# 10A_Current_Sensor_v1_0.net
KiCad netlist of a schematic drawn in EAGLE
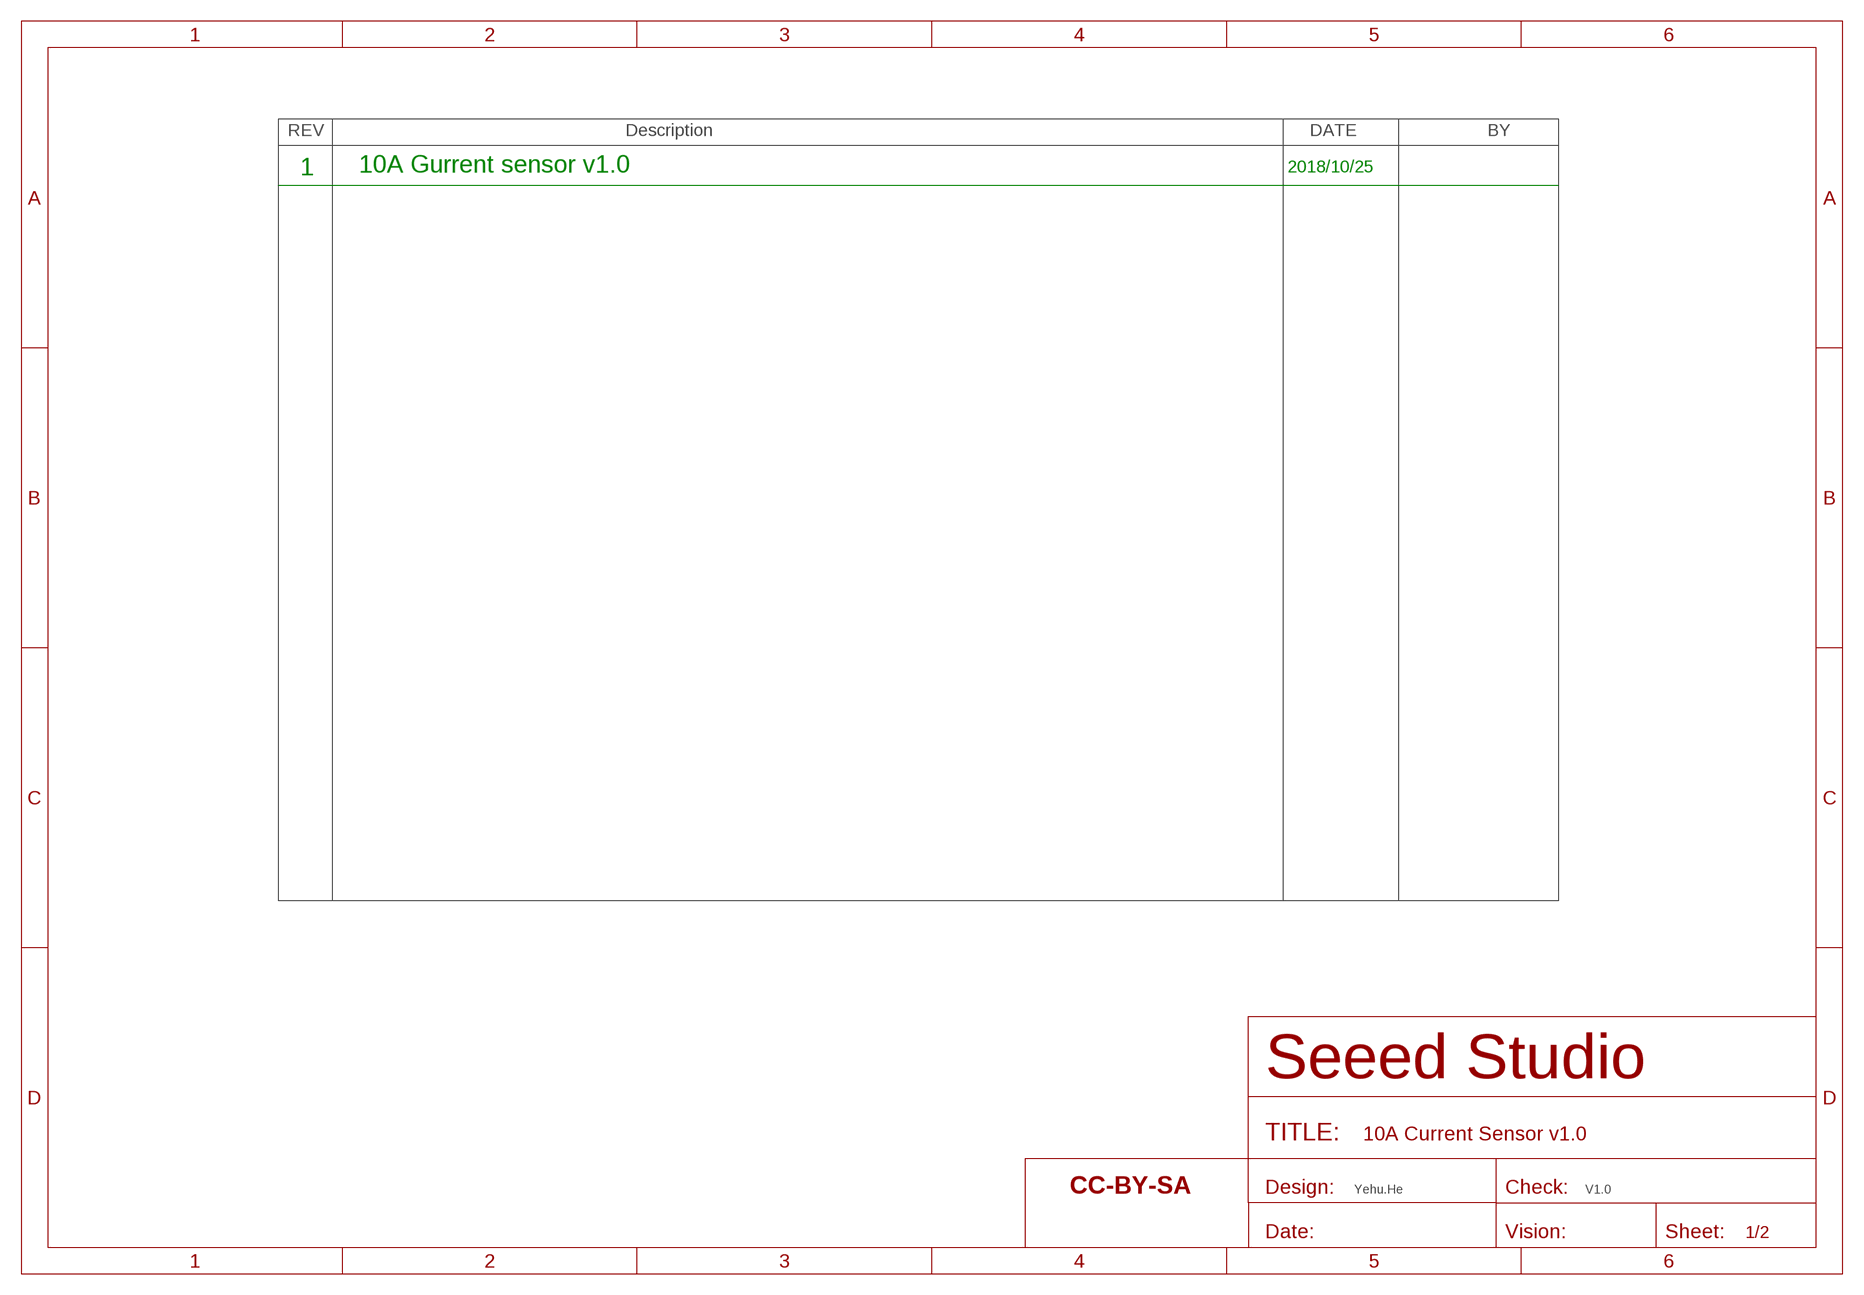
[diagram p0: schematic, sheet 1]
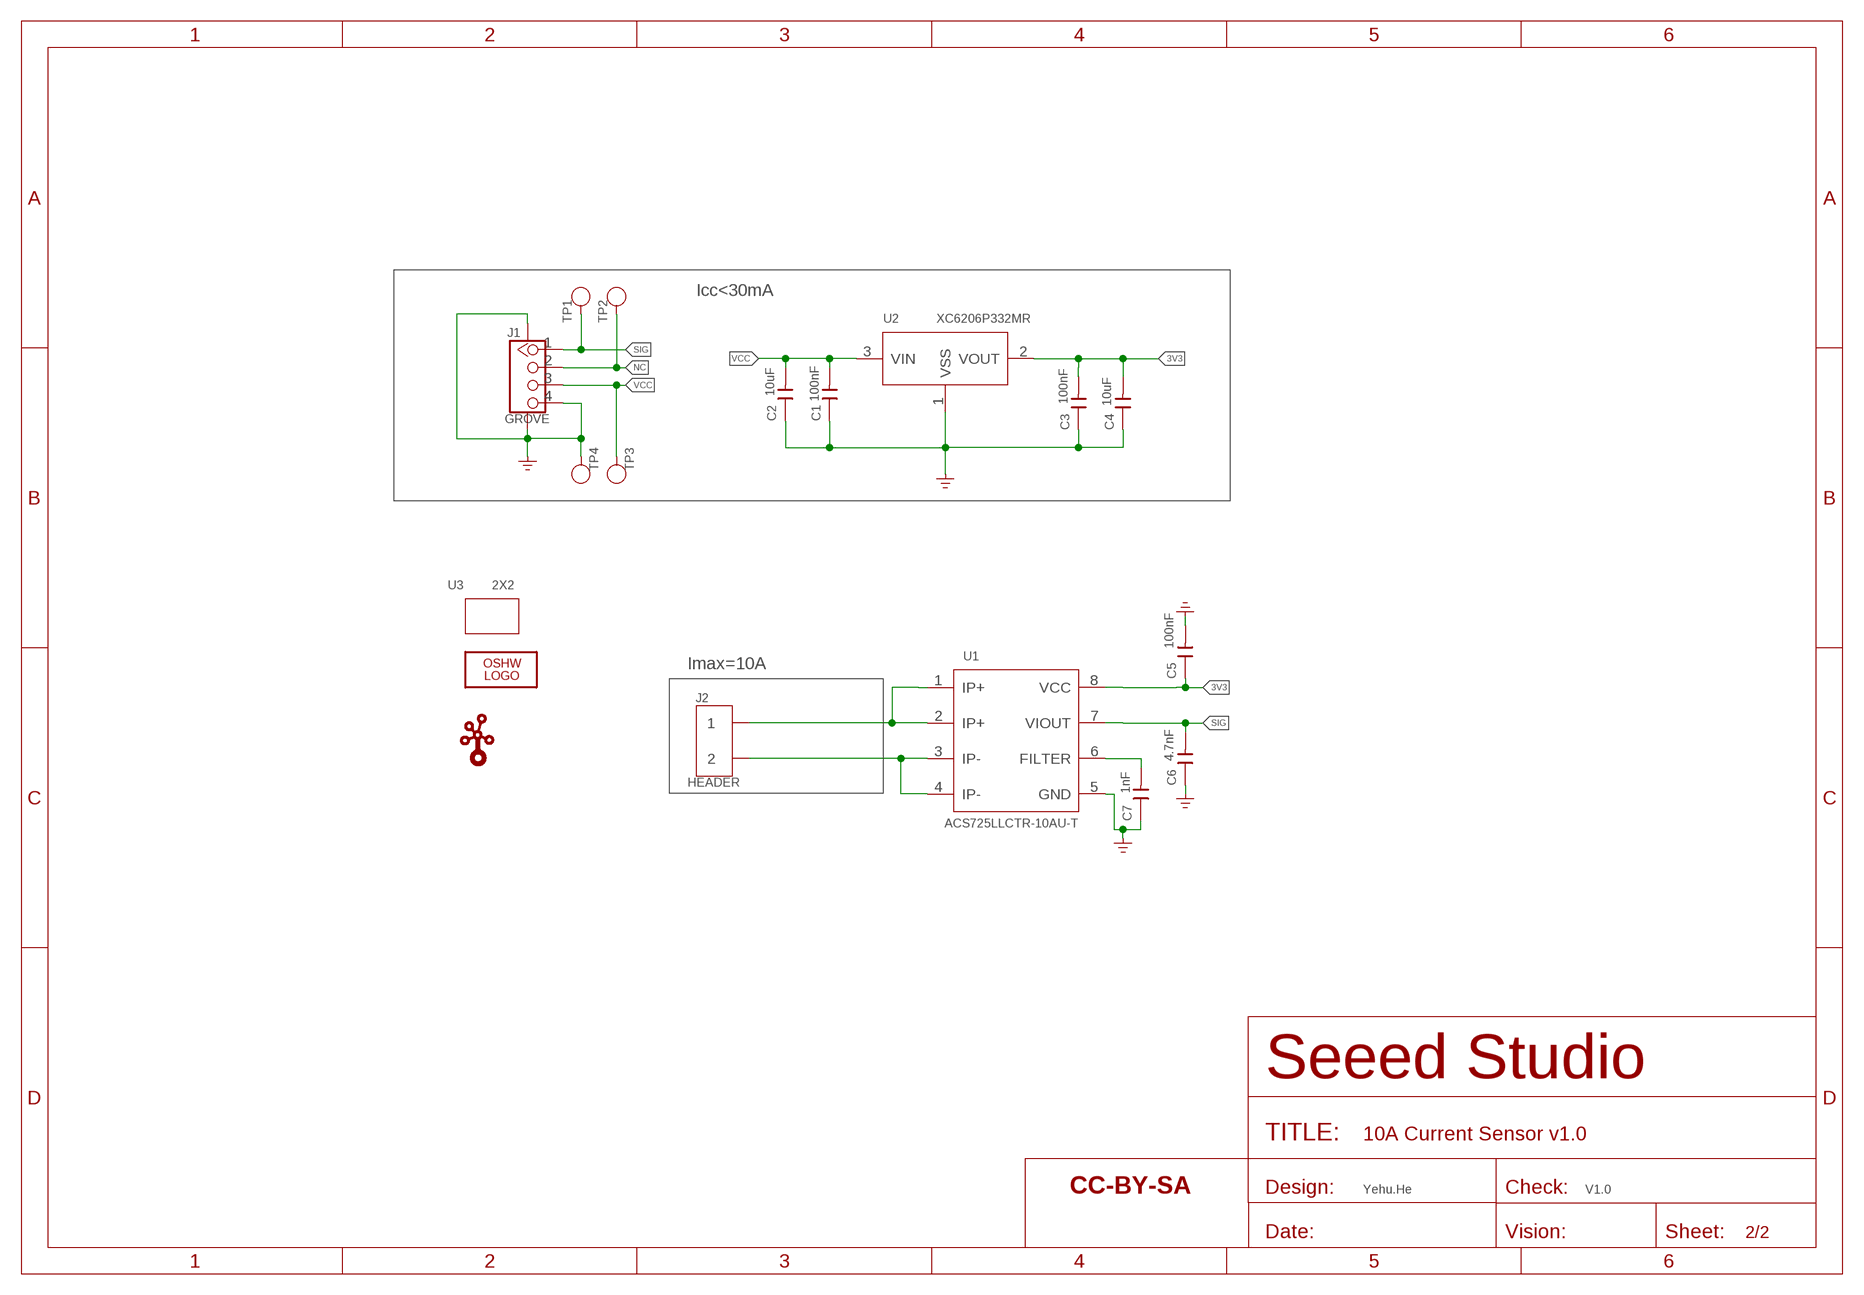
[diagram p1: schematic, sheet 2]

(export (version "E")
  (design (tool "Eeschema 10.0.6"))
  (components
    (comp (ref "C1")
      (value "100nF")
      (footprint "eagle-import:C0603")
      (libsource (lib "eagle-import") (part "CAP-0603"))
    )
    (comp (ref "C2")
      (value "10uF")
      (footprint "eagle-import:C0603")
      (libsource (lib "eagle-import") (part "CAP-0603"))
    )
    (comp (ref "C3")
      (value "100nF")
      (footprint "eagle-import:C0603")
      (libsource (lib "eagle-import") (part "CAP-0603"))
    )
    (comp (ref "C4")
      (value "10uF")
      (footprint "eagle-import:C0603")
      (libsource (lib "eagle-import") (part "CAP-0603"))
    )
    (comp (ref "C5")
      (value "100nF")
      (footprint "eagle-import:C0603")
      (libsource (lib "eagle-import") (part "CAP-0603"))
    )
    (comp (ref "C6")
      (value "4.7nF")
      (footprint "eagle-import:C0603")
      (libsource (lib "eagle-import") (part "CAP-0603"))
    )
    (comp (ref "C7")
      (value "1nF")
      (footprint "eagle-import:C0603")
      (libsource (lib "eagle-import") (part "CAP-0603"))
    )
    (comp (ref "FR2")
      (value "SEEEDSTUDIO-OPEN-SCH-FRAME")
      (footprint "eagle-import:SEEEDSTUDIO-PCB-FRAME")
      (libsource (lib "eagle-import") (part "SEEEDSTUDIO-OPEN-SCH-FRAME"))
    )
    (comp (ref "J1")
      (value "GROVE")
      (footprint "eagle-import:HW4-SMD-2.0")
      (libsource (lib "eagle-import") (part "GROVE-CONNECTOR-SMD'DD'"))
    )
    (comp (ref "J2")
      (value "HEADER")
      (footprint "eagle-import:H2-5.0-10.5X8.0MM")
      (libsource (lib "eagle-import") (part "SCREW-TERMINAL-2P'5.08'"))
    )
    (comp (ref "LOGO1")
      (value "LOGO-OSHW-FILLX0200-NT")
      (footprint "eagle-import:OSHW_FILLX200_NOTEXT")
      (fields (field (name "PARTNO") "DNP"))
      (libsource (lib "eagle-import") (part "LOGO-OSHW-FILLX0200-NT"))
    )
    (comp (ref "TP1")
      (value "TEST")
      (footprint "eagle-import:TP-D45MIL")
      (fields (field (name "PARTNO") "DNP"))
      (libsource (lib "eagle-import") (part "TEST-POINT'4545'"))
    )
    (comp (ref "TP2")
      (value "TEST")
      (footprint "eagle-import:TP-D45MIL")
      (fields (field (name "PARTNO") "DNP"))
      (libsource (lib "eagle-import") (part "TEST-POINT'4545'"))
    )
    (comp (ref "TP3")
      (value "TEST")
      (footprint "eagle-import:TP-D45MIL")
      (fields (field (name "PARTNO") "DNP"))
      (libsource (lib "eagle-import") (part "TEST-POINT'4545'"))
    )
    (comp (ref "TP4")
      (value "TEST")
      (footprint "eagle-import:TP-D45MIL")
      (fields (field (name "PARTNO") "DNP"))
      (libsource (lib "eagle-import") (part "TEST-POINT'4545'"))
    )
    (comp (ref "U$7")
      (value "LOGO-GROVE")
      (footprint "eagle-import:GROVE-SILK-BIG")
      (fields (field (name "PARTNO") "DNP"))
      (libsource (lib "eagle-import") (part "LOGO-GROVE"))
    )
    (comp (ref "U1")
      (value "ACS725LLCTR-10AU-T")
      (footprint "eagle-import:SOIC8-1.27-5X4MM")
      (libsource (lib "eagle-import") (part "SENSOR-ACS725"))
    )
    (comp (ref "U2")
      (value "XC6206P332MR")
      (footprint "eagle-import:SOT-23")
      (libsource (lib "eagle-import") (part "PMIC-XC6206PMR"))
    )
    (comp (ref "U3")
      (value "2X2")
      (footprint "eagle-import:GROVE-1_2-TEST-PLATFORM-TOP")
      (libsource (lib "eagle-import") (part "GROVE-1X2-TOP"))
    )
    (comp (ref "FR1")
      (value "SEEEDSTUDIO-OPEN-SCH-FRAME")
      (footprint "eagle-import:SEEEDSTUDIO-PCB-FRAME")
      (libsource (lib "eagle-import") (part "SEEEDSTUDIO-OPEN-SCH-FRAME"))
    )
  )
  (nets
    (net (code "1") (name "3V3") (class "Default")
      (node (ref "C3") (pin "2") (pinfunction "2_2") (pintype "passive"))
      (node (ref "C4") (pin "2") (pinfunction "2_2") (pintype "passive"))
      (node (ref "C5") (pin "1") (pinfunction "1_1") (pintype "passive"))
      (node (ref "U1") (pin "8") (pinfunction "VCC_8") (pintype "bidirectional"))
      (node (ref "U2") (pin "2") (pinfunction "VOUT_2") (pintype "bidirectional"))
    )
    (net (code "2") (name "GND") (class "Default")
      (node (ref "C1") (pin "1") (pinfunction "1_1") (pintype "passive"))
      (node (ref "C2") (pin "1") (pinfunction "1_1") (pintype "passive"))
      (node (ref "C3") (pin "1") (pinfunction "1_1") (pintype "passive"))
      (node (ref "C4") (pin "1") (pinfunction "1_1") (pintype "passive"))
      (node (ref "C5") (pin "2") (pinfunction "2_2") (pintype "passive"))
      (node (ref "C6") (pin "1") (pinfunction "1_1") (pintype "passive"))
      (node (ref "C7") (pin "1") (pinfunction "1_1") (pintype "passive"))
      (node (ref "J1") (pin "4") (pinfunction "4_4") (pintype "bidirectional"))
      (node (ref "J1") (pin "SS1") (pinfunction "SS1_SS1") (pintype "bidirectional"))
      (node (ref "J1") (pin "SS2") (pinfunction "SS2_SS2") (pintype "bidirectional"))
      (node (ref "TP4") (pin "T") (pinfunction "T_T") (pintype "bidirectional"))
      (node (ref "U1") (pin "5") (pinfunction "GND_5") (pintype "bidirectional"))
      (node (ref "U2") (pin "1") (pinfunction "VSS_1") (pintype "bidirectional"))
    )
    (net (code "3") (name "NC") (class "Default")
      (node (ref "J1") (pin "2") (pinfunction "2_2") (pintype "bidirectional"))
      (node (ref "TP2") (pin "T") (pinfunction "T_T") (pintype "bidirectional"))
    )
    (net (code "4") (name "Net-(J2-Pad1)") (class "Default")
      (node (ref "J2") (pin "1") (pinfunction "1_1") (pintype "bidirectional"))
      (node (ref "U1") (pin "1") (pinfunction "IP+_1") (pintype "bidirectional"))
      (node (ref "U1") (pin "2") (pinfunction "IP+_2") (pintype "bidirectional"))
    )
    (net (code "5") (name "Net-(J2-Pad2)") (class "Default")
      (node (ref "J2") (pin "2") (pinfunction "2_2") (pintype "bidirectional"))
      (node (ref "U1") (pin "3") (pinfunction "IP-_3") (pintype "bidirectional"))
      (node (ref "U1") (pin "4") (pinfunction "IP-_4") (pintype "bidirectional"))
    )
    (net (code "6") (name "Net-(U1-FILTER)") (class "Default")
      (node (ref "C7") (pin "2") (pinfunction "2_2") (pintype "passive"))
      (node (ref "U1") (pin "6") (pinfunction "FILTER_6") (pintype "bidirectional"))
    )
    (net (code "7") (name "SIG") (class "Default")
      (node (ref "C6") (pin "2") (pinfunction "2_2") (pintype "passive"))
      (node (ref "J1") (pin "1") (pinfunction "1_1") (pintype "bidirectional"))
      (node (ref "TP1") (pin "T") (pinfunction "T_T") (pintype "bidirectional"))
      (node (ref "U1") (pin "7") (pinfunction "VIOUT_7") (pintype "bidirectional"))
    )
    (net (code "8") (name "VCC") (class "Default")
      (node (ref "C1") (pin "2") (pinfunction "2_2") (pintype "passive"))
      (node (ref "C2") (pin "2") (pinfunction "2_2") (pintype "passive"))
      (node (ref "J1") (pin "3") (pinfunction "3_3") (pintype "bidirectional"))
      (node (ref "TP3") (pin "T") (pinfunction "T_T") (pintype "bidirectional"))
      (node (ref "U2") (pin "3") (pinfunction "VIN_3") (pintype "bidirectional"))
    )
  )
)
